# CPU-board-Sheet3-multi.net
KiCad netlist of a schematic drawn in Altium Designer
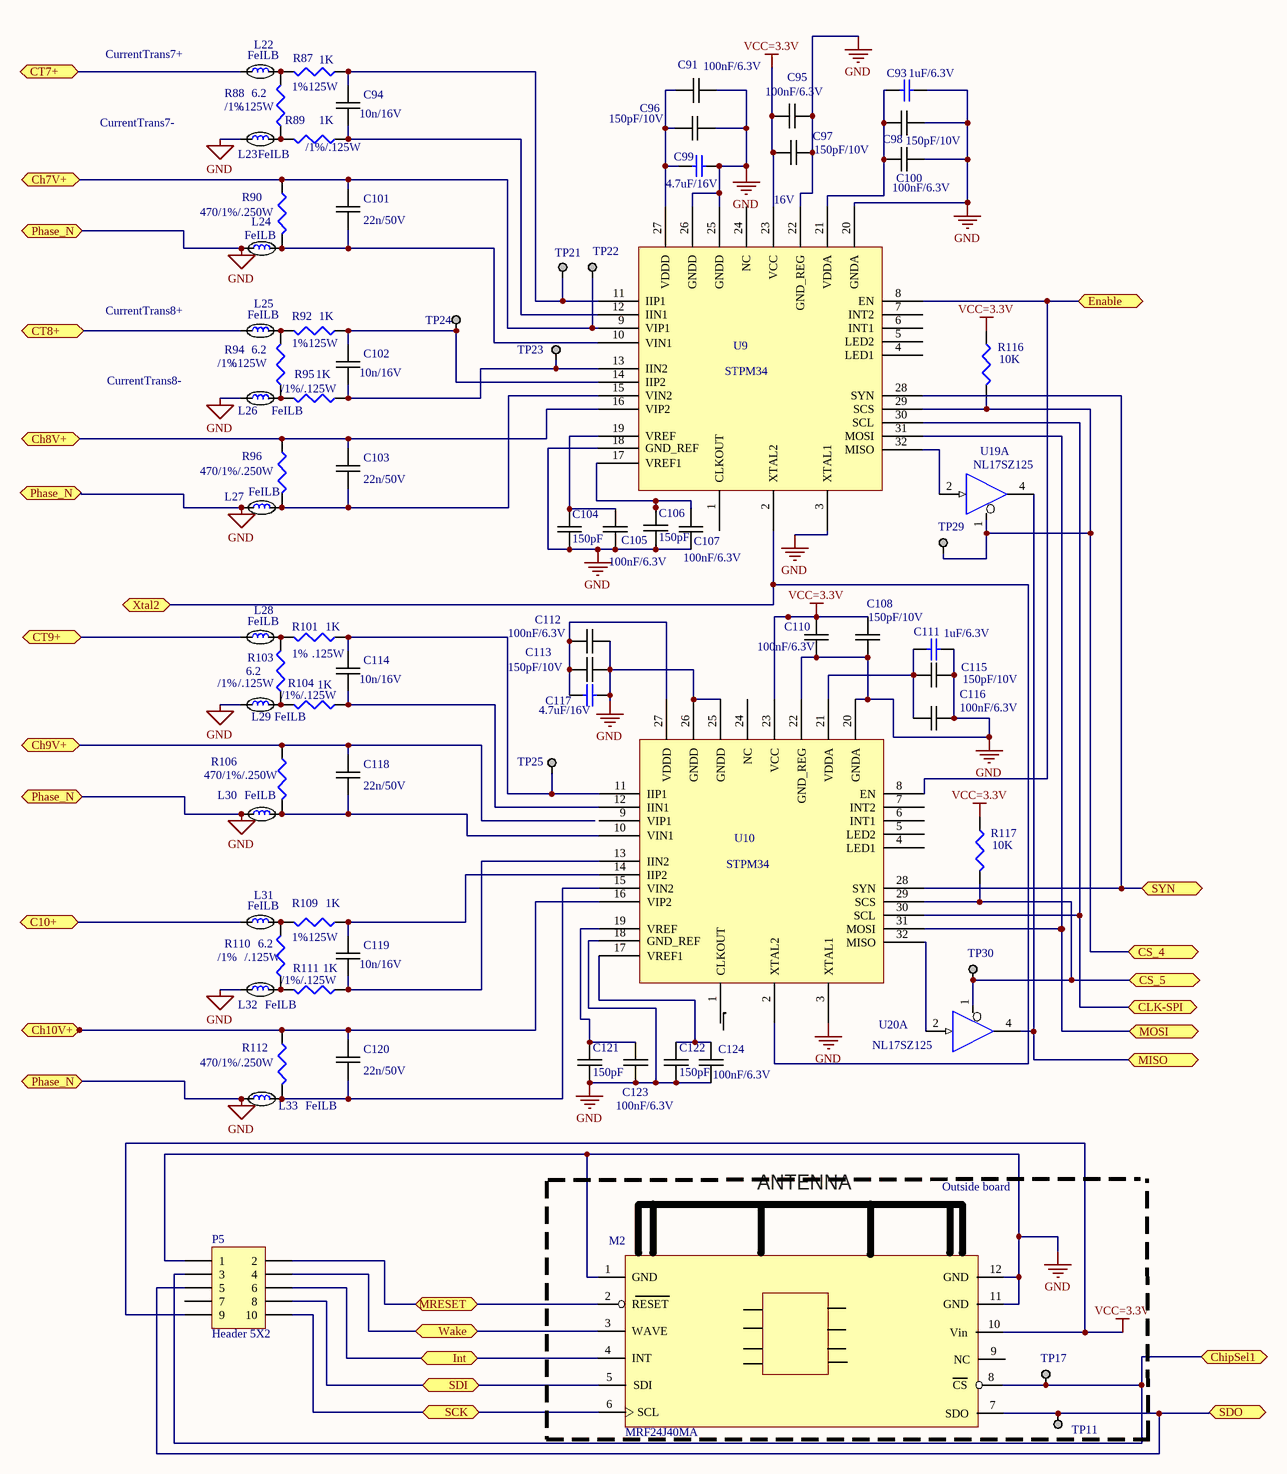
[diagram p0: CPU-board-Sheet3-multi.SchDoc]

(export (version "E")
  (design (tool "Eeschema 10.0.6"))
  (components
    (comp (ref "C91")
      (value "100nF/6.3V")
      (footprint "0402C-GENERIC")
      (description "CAPACITOR 0805 CERAMIC")
      (fields (field (name "MANUFACTURER") "Taiyo Yuden"))
      (libsource (lib "vh_altium_library") (part "0805C-18PF-50V-C0G-JOH"))
    )
    (comp (ref "C93")
      (value "1uF/6.3V")
      (footprint "0402C-GENERIC")
      (description "Capacitor")
      (fields (field (name "MANUFACTURER") "Murata") (field (name "PUBLISHER") "Altium Limited"))
      (libsource (lib "Miscellaneous Devices") (part "Cap"))
    )
    (comp (ref "C94")
      (value "10n/16V")
      (footprint "0402C-GENERIC")
      (description "CAPACITOR 0805 CERAMIC")
      (fields (field (name "MANUFACTURER") "Murata Electronics"))
      (libsource (lib "vh_altium_library") (part "0805C-18PF-50V-C0G-JOH"))
    )
    (comp (ref "C95")
      (value "100nF/6.3V")
      (footprint "0402C-GENERIC")
      (description "CAPACITOR 0805 CERAMIC")
      (fields (field (name "MANUFACTURER") "Taiyo Yuden"))
      (libsource (lib "vh_altium_library") (part "0805C-18PF-50V-C0G-JOH"))
    )
    (comp (ref "C96")
      (value "150pF/10V")
      (footprint "0402C-GENERIC")
      (description "CAPACITOR 0805 CERAMIC")
      (fields (field (name "MANUFACTURER") "Wurth Electronics"))
      (libsource (lib "vh_altium_library") (part "0805C-18PF-50V-C0G-JOH"))
    )
    (comp (ref "C97")
      (value "150pF/10V")
      (footprint "0402C-GENERIC")
      (description "CAPACITOR 0805 CERAMIC")
      (fields (field (name "MANUFACTURER") "Wurth Electronics"))
      (libsource (lib "vh_altium_library") (part "0805C-18PF-50V-C0G-JOH"))
    )
    (comp (ref "C98")
      (value "150pF/10V")
      (footprint "0402C-GENERIC")
      (description "CAPACITOR 0805 CERAMIC")
      (fields (field (name "MANUFACTURER") "Wurth Electronics"))
      (libsource (lib "vh_altium_library") (part "0805C-18PF-50V-C0G-JOH"))
    )
    (comp (ref "C99")
      (value "4.7uF/16V")
      (footprint "0402C-GENERIC")
      (description "Capacitor")
      (fields (field (name "MANUFACTURER") "Samsung") (field (name "PUBLISHER") "Altium Limited"))
      (libsource (lib "Miscellaneous Devices") (part "Cap"))
    )
    (comp (ref "C100")
      (value "100nF/6.3V")
      (footprint "0402C-GENERIC")
      (description "CAPACITOR 0805 CERAMIC")
      (fields (field (name "MANUFACTURER") "Taiyo Yuden"))
      (libsource (lib "vh_altium_library") (part "0805C-18PF-50V-C0G-JOH"))
    )
    (comp (ref "C101")
      (value "22n/50V")
      (footprint "0402C-GENERIC")
      (description "CAPACITOR 0805 CERAMIC")
      (fields (field (name "MANUFACTURER") "Murata Electronics"))
      (libsource (lib "vh_altium_library") (part "0805C-18PF-50V-C0G-JOH"))
    )
    (comp (ref "C102")
      (value "10n/16V")
      (footprint "0402C-GENERIC")
      (description "CAPACITOR 0805 CERAMIC")
      (fields (field (name "MANUFACTURER") "Murata Electronics"))
      (libsource (lib "vh_altium_library") (part "0805C-18PF-50V-C0G-JOH"))
    )
    (comp (ref "C103")
      (value "22n/50V")
      (footprint "0402C-GENERIC")
      (description "CAPACITOR 0805 CERAMIC")
      (fields (field (name "MANUFACTURER") "Murata Electronics"))
      (libsource (lib "vh_altium_library") (part "0805C-18PF-50V-C0G-JOH"))
    )
    (comp (ref "C104")
      (value "150pF")
      (footprint "0402C-GENERIC")
      (description "CAPACITOR 0805 CERAMIC")
      (fields (field (name "MANUFACTURER") "Wurth Electronics"))
      (libsource (lib "vh_altium_library") (part "0805C-18PF-50V-C0G-JOH"))
    )
    (comp (ref "C105")
      (value "100nF/6.3V")
      (footprint "0402C-GENERIC")
      (description "CAPACITOR 0805 CERAMIC")
      (fields (field (name "MANUFACTURER") "Taiyo Yuden"))
      (libsource (lib "vh_altium_library") (part "0805C-18PF-50V-C0G-JOH"))
    )
    (comp (ref "C106")
      (value "150pF")
      (footprint "0402C-GENERIC")
      (description "CAPACITOR 0805 CERAMIC")
      (fields (field (name "MANUFACTURER") "Wurth Electronics"))
      (libsource (lib "vh_altium_library") (part "0805C-18PF-50V-C0G-JOH"))
    )
    (comp (ref "C107")
      (value "100nF/6.3V")
      (footprint "0402C-GENERIC")
      (description "CAPACITOR 0805 CERAMIC")
      (fields (field (name "MANUFACTURER") "Taiyo Yuden"))
      (libsource (lib "vh_altium_library") (part "0805C-18PF-50V-C0G-JOH"))
    )
    (comp (ref "C108")
      (value "150pF/10V")
      (footprint "0402C-GENERIC")
      (description "CAPACITOR 0805 CERAMIC")
      (fields (field (name "MANUFACTURER") "Wurth Electronics"))
      (libsource (lib "vh_altium_library") (part "0805C-18PF-50V-C0G-JOH"))
    )
    (comp (ref "C110")
      (value "100nF/6.3V")
      (footprint "0402C-GENERIC")
      (description "CAPACITOR 0805 CERAMIC")
      (fields (field (name "MANUFACTURER") "Taiyo Yuden"))
      (libsource (lib "vh_altium_library") (part "0805C-18PF-50V-C0G-JOH"))
    )
    (comp (ref "C111")
      (value "1uF/6.3V")
      (footprint "0402C-GENERIC")
      (description "Capacitor")
      (fields (field (name "MANUFACTURER") "Murata") (field (name "PUBLISHER") "Altium Limited"))
      (libsource (lib "Miscellaneous Devices") (part "Cap"))
    )
    (comp (ref "C112")
      (value "100nF/6.3V")
      (footprint "0402C-GENERIC")
      (description "CAPACITOR 0805 CERAMIC")
      (fields (field (name "MANUFACTURER") "Taiyo Yuden"))
      (libsource (lib "vh_altium_library") (part "0805C-18PF-50V-C0G-JOH"))
    )
    (comp (ref "C113")
      (value "150pF/10V")
      (footprint "0402C-GENERIC")
      (description "CAPACITOR 0805 CERAMIC")
      (fields (field (name "MANUFACTURER") "Wurth Electronics"))
      (libsource (lib "vh_altium_library") (part "0805C-18PF-50V-C0G-JOH"))
    )
    (comp (ref "C114")
      (value "10n/16V")
      (footprint "0402C-GENERIC")
      (description "CAPACITOR 0805 CERAMIC")
      (fields (field (name "MANUFACTURER") "Murata Electronics"))
      (libsource (lib "vh_altium_library") (part "0805C-18PF-50V-C0G-JOH"))
    )
    (comp (ref "C115")
      (value "150pF/10V")
      (footprint "0402C-GENERIC")
      (description "CAPACITOR 0805 CERAMIC")
      (fields (field (name "MANUFACTURER") "Wurth Electronics"))
      (libsource (lib "vh_altium_library") (part "0805C-18PF-50V-C0G-JOH"))
    )
    (comp (ref "C116")
      (value "100nF/6.3V")
      (footprint "0402C-GENERIC")
      (description "CAPACITOR 0805 CERAMIC")
      (fields (field (name "MANUFACTURER") "Taiyo Yuden"))
      (libsource (lib "vh_altium_library") (part "0805C-18PF-50V-C0G-JOH"))
    )
    (comp (ref "C117")
      (value "4.7uF/16V")
      (footprint "0402C-GENERIC")
      (description "Capacitor")
      (fields (field (name "MANUFACTURER") "Samsung") (field (name "PUBLISHER") "Altium Limited"))
      (libsource (lib "Miscellaneous Devices") (part "Cap"))
    )
    (comp (ref "C118")
      (value "22n/50V")
      (footprint "0402C-GENERIC")
      (description "CAPACITOR 0805 CERAMIC")
      (fields (field (name "MANUFACTURER") "Murata Electronics"))
      (libsource (lib "vh_altium_library") (part "0805C-18PF-50V-C0G-JOH"))
    )
    (comp (ref "C119")
      (value "10n/16V")
      (footprint "0402C-GENERIC")
      (description "CAPACITOR 0805 CERAMIC")
      (fields (field (name "MANUFACTURER") "Murata Electronics"))
      (libsource (lib "vh_altium_library") (part "0805C-18PF-50V-C0G-JOH"))
    )
    (comp (ref "C120")
      (value "22n/50V")
      (footprint "0402C-GENERIC")
      (description "CAPACITOR 0805 CERAMIC")
      (fields (field (name "MANUFACTURER") "Murata Electronics"))
      (libsource (lib "vh_altium_library") (part "0805C-18PF-50V-C0G-JOH"))
    )
    (comp (ref "C121")
      (value "150pF")
      (footprint "0402C-GENERIC")
      (description "CAPACITOR 0805 CERAMIC")
      (fields (field (name "MANUFACTURER") "Wurth Electronics"))
      (libsource (lib "vh_altium_library") (part "0805C-18PF-50V-C0G-JOH"))
    )
    (comp (ref "C122")
      (value "150pF")
      (footprint "0402C-GENERIC")
      (description "CAPACITOR 0805 CERAMIC")
      (fields (field (name "MANUFACTURER") "Wurth Electronics"))
      (libsource (lib "vh_altium_library") (part "0805C-18PF-50V-C0G-JOH"))
    )
    (comp (ref "C123")
      (value "100nF/6.3V")
      (footprint "0402C-GENERIC")
      (description "CAPACITOR 0805 CERAMIC")
      (fields (field (name "MANUFACTURER") "Taiyo Yuden"))
      (libsource (lib "vh_altium_library") (part "0805C-18PF-50V-C0G-JOH"))
    )
    (comp (ref "C124")
      (value "100nF/6.3V")
      (footprint "0402C-GENERIC")
      (description "CAPACITOR 0805 CERAMIC")
      (fields (field (name "MANUFACTURER") "Taiyo Yuden"))
      (libsource (lib "vh_altium_library") (part "0805C-18PF-50V-C0G-JOH"))
    )
    (comp (ref "L22")
      (value "FeILB")
      (footprint "0603C-TBD")
      (fields (field (name "MANUFACTURER") "Brand Samsung"))
      (libsource (lib "SMLib") (part "FerrBeads/ILBB"))
    )
    (comp (ref "L23")
      (value "FeILB")
      (footprint "0603C-TBD")
      (fields (field (name "MANUFACTURER") "Brand Samsung"))
      (libsource (lib "SMLib") (part "FerrBeads/ILBB"))
    )
    (comp (ref "L24")
      (value "FeILB")
      (footprint "0603C-TBD")
      (fields (field (name "MANUFACTURER") "Brand Samsung"))
      (libsource (lib "SMLib") (part "FerrBeads/ILBB"))
    )
    (comp (ref "L25")
      (value "FeILB")
      (footprint "0603C-TBD")
      (fields (field (name "MANUFACTURER") "Brand Samsung"))
      (libsource (lib "SMLib") (part "FerrBeads/ILBB"))
    )
    (comp (ref "L26")
      (value "FeILB")
      (footprint "0603C-TBD")
      (fields (field (name "MANUFACTURER") "Brand Samsung"))
      (libsource (lib "SMLib") (part "FerrBeads/ILBB"))
    )
    (comp (ref "L27")
      (value "FeILB")
      (footprint "0603C-TBD")
      (fields (field (name "MANUFACTURER") "Brand Samsung"))
      (libsource (lib "SMLib") (part "FerrBeads/ILBB"))
    )
    (comp (ref "L28")
      (value "FeILB")
      (footprint "0603C-TBD")
      (fields (field (name "MANUFACTURER") "Brand Samsung"))
      (libsource (lib "SMLib") (part "FerrBeads/ILBB"))
    )
    (comp (ref "L29")
      (value "FeILB")
      (footprint "0603C-TBD")
      (fields (field (name "MANUFACTURER") "Brand Samsung"))
      (libsource (lib "SMLib") (part "FerrBeads/ILBB"))
    )
    (comp (ref "L30")
      (value "FeILB")
      (footprint "0603C-TBD")
      (fields (field (name "MANUFACTURER") "Brand Samsung"))
      (libsource (lib "SMLib") (part "FerrBeads/ILBB"))
    )
    (comp (ref "L31")
      (value "FeILB")
      (footprint "0603C-TBD")
      (fields (field (name "MANUFACTURER") "Brand Samsung"))
      (libsource (lib "SMLib") (part "FerrBeads/ILBB"))
    )
    (comp (ref "L32")
      (value "FeILB")
      (footprint "0603C-TBD")
      (fields (field (name "MANUFACTURER") "Brand Samsung"))
      (libsource (lib "SMLib") (part "FerrBeads/ILBB"))
    )
    (comp (ref "L33")
      (value "FeILB")
      (footprint "0603C-TBD")
      (fields (field (name "MANUFACTURER") "Brand Samsung"))
      (libsource (lib "SMLib") (part "FerrBeads/ILBB"))
    )
    (comp (ref "M2")
      (value "MRF24J40MA")
      (footprint "MRF24J40MA-zigBEE module")
      (fields (field (name "MANUFACTURER") "Microchip"))
      (libsource (lib "SMLib") (part "MRF24J40MA"))
    )
    (comp (ref "P5")
      (value "Header 5X2")
      (footprint "Header2x5 1.27mm pitch")
      (description "Header, 5-Pin, Dual row")
      (fields (field (name "MANUFACTURER") "Samtec Inc") (field (name "PUBLISHER") "Altium Limited"))
      (libsource (lib "Miscellaneous Connectors") (part "Header 5X2"))
    )
    (comp (ref "R87")
      (value "1K")
      (footprint "0402R-TBD")
      (description "Resistor")
      (fields (field (name "MANUFACTURER") "Panasonic") (field (name "PUBLISHER") "Altium Limited"))
      (libsource (lib "Miscellaneous Devices") (part "Res3"))
    )
    (comp (ref "R88")
      (value "6.2")
      (footprint "0402R-TBD")
      (description "Resistor")
      (fields (field (name "MANUFACTURER") "Vishay Dale") (field (name "PUBLISHER") "Altium Limited"))
      (libsource (lib "Miscellaneous Devices") (part "Res3"))
    )
    (comp (ref "R89")
      (value "1K")
      (footprint "0402R-TBD")
      (description "Resistor")
      (fields (field (name "MANUFACTURER") "Panasonic") (field (name "PUBLISHER") "Altium Limited"))
      (libsource (lib "Miscellaneous Devices") (part "Res3"))
    )
    (comp (ref "R90")
      (value "470/1%/.250W")
      (footprint "1206FB-GENERIC")
      (description "Resistor")
      (fields (field (name "MANUFACTURER") "Vishay/Draloric") (field (name "PUBLISHER") "Altium Limited"))
      (libsource (lib "Miscellaneous Devices") (part "Res3"))
    )
    (comp (ref "R92")
      (value "1K")
      (footprint "0402R-TBD")
      (description "Resistor")
      (fields (field (name "MANUFACTURER") "Panasonic") (field (name "PUBLISHER") "Altium Limited"))
      (libsource (lib "Miscellaneous Devices") (part "Res3"))
    )
    (comp (ref "R94")
      (value "6.2")
      (footprint "0402R-TBD")
      (description "Resistor")
      (fields (field (name "MANUFACTURER") "Vishay Dale") (field (name "PUBLISHER") "Altium Limited"))
      (libsource (lib "Miscellaneous Devices") (part "Res3"))
    )
    (comp (ref "R95")
      (value "1K")
      (footprint "0402R-TBD")
      (description "Resistor")
      (fields (field (name "MANUFACTURER") "Panasonic") (field (name "PUBLISHER") "Altium Limited"))
      (libsource (lib "Miscellaneous Devices") (part "Res3"))
    )
    (comp (ref "R96")
      (value "470/1%/.250W")
      (footprint "1206FB-GENERIC")
      (description "Resistor")
      (fields (field (name "MANUFACTURER") "Vishay/Draloric") (field (name "PUBLISHER") "Altium Limited"))
      (libsource (lib "Miscellaneous Devices") (part "Res3"))
    )
    (comp (ref "R101")
      (value "1K")
      (footprint "0402R-TBD")
      (description "Resistor")
      (fields (field (name "MANUFACTURER") "Panasonic") (field (name "PUBLISHER") "Altium Limited"))
      (libsource (lib "Miscellaneous Devices") (part "Res3"))
    )
    (comp (ref "R103")
      (value "6.2")
      (footprint "0402R-TBD")
      (description "Resistor")
      (fields (field (name "MANUFACTURER") "Vishay Dale") (field (name "PUBLISHER") "Altium Limited"))
      (libsource (lib "Miscellaneous Devices") (part "Res3"))
    )
    (comp (ref "R104")
      (value "1K")
      (footprint "0402R-TBD")
      (description "Resistor")
      (fields (field (name "MANUFACTURER") "Panasonic") (field (name "PUBLISHER") "Altium Limited"))
      (libsource (lib "Miscellaneous Devices") (part "Res3"))
    )
    (comp (ref "R106")
      (value "470/1%/.250W")
      (footprint "1206FB-GENERIC")
      (description "Resistor")
      (fields (field (name "MANUFACTURER") "Vishay/Draloric") (field (name "PUBLISHER") "Altium Limited"))
      (libsource (lib "Miscellaneous Devices") (part "Res3"))
    )
    (comp (ref "R109")
      (value "1K")
      (footprint "0402R-TBD")
      (description "Resistor")
      (fields (field (name "MANUFACTURER") "Panasonic") (field (name "PUBLISHER") "Altium Limited"))
      (libsource (lib "Miscellaneous Devices") (part "Res3"))
    )
    (comp (ref "R110")
      (value "6.2")
      (footprint "0402R-TBD")
      (description "Resistor")
      (fields (field (name "MANUFACTURER") "Vishay Dale") (field (name "PUBLISHER") "Altium Limited"))
      (libsource (lib "Miscellaneous Devices") (part "Res3"))
    )
    (comp (ref "R111")
      (value "1K")
      (footprint "0402R-TBD")
      (description "Resistor")
      (fields (field (name "MANUFACTURER") "Panasonic") (field (name "PUBLISHER") "Altium Limited"))
      (libsource (lib "Miscellaneous Devices") (part "Res3"))
    )
    (comp (ref "R112")
      (value "470/1%/.250W")
      (footprint "1206FB-GENERIC")
      (description "Resistor")
      (fields (field (name "MANUFACTURER") "Vishay/Draloric") (field (name "PUBLISHER") "Altium Limited"))
      (libsource (lib "Miscellaneous Devices") (part "Res3"))
    )
    (comp (ref "R116")
      (value "10K")
      (footprint "0402C-GENERIC")
      (description "Resistor")
      (fields (field (name "MANUFACTURER") "Panasonic") (field (name "PUBLISHER") "Altium Limited"))
      (libsource (lib "Miscellaneous Devices") (part "Res3"))
    )
    (comp (ref "R117")
      (value "10K")
      (footprint "0402C-GENERIC")
      (description "Resistor")
      (fields (field (name "MANUFACTURER") "Panasonic") (field (name "PUBLISHER") "Altium Limited"))
      (libsource (lib "Miscellaneous Devices") (part "Res3"))
    )
    (comp (ref "TP11")
      (value "TESTPOINT")
      (footprint "TESTPOINT")
      (description "TESTPOINT SCOPE GRABBER")
      (fields
        (field (name "MANUFACTURER PART NUMBER") "5010")
        (field (name "MANUFACTURER") "Keystone Electronics")
      )
      (libsource (lib "vh_altium_library") (part "TESTPOINT"))
    )
    (comp (ref "TP17")
      (value "TESTPOINT")
      (footprint "TESTPOINT")
      (description "TESTPOINT SCOPE GRABBER")
      (fields
        (field (name "MANUFACTURER PART NUMBER") "5010")
        (field (name "MANUFACTURER") "Keystone Electronics")
      )
      (libsource (lib "vh_altium_library") (part "TESTPOINT"))
    )
    (comp (ref "TP21")
      (value "TESTPOINT")
      (footprint "TESTPOINT")
      (description "TESTPOINT SCOPE GRABBER")
      (fields
        (field (name "MANUFACTURER PART NUMBER") "5010")
        (field (name "MANUFACTURER") "Keystone Electronics")
      )
      (libsource (lib "vh_altium_library") (part "TESTPOINT"))
    )
    (comp (ref "TP22")
      (value "TESTPOINT")
      (footprint "TESTPOINT")
      (description "TESTPOINT SCOPE GRABBER")
      (fields
        (field (name "MANUFACTURER PART NUMBER") "5010")
        (field (name "MANUFACTURER") "Keystone Electronics")
      )
      (libsource (lib "vh_altium_library") (part "TESTPOINT"))
    )
    (comp (ref "TP23")
      (value "TESTPOINT")
      (footprint "TESTPOINT")
      (description "TESTPOINT SCOPE GRABBER")
      (fields
        (field (name "MANUFACTURER PART NUMBER") "5010")
        (field (name "MANUFACTURER") "Keystone Electronics")
      )
      (libsource (lib "vh_altium_library") (part "TESTPOINT"))
    )
    (comp (ref "TP24")
      (value "TESTPOINT")
      (footprint "TESTPOINT")
      (description "TESTPOINT SCOPE GRABBER")
      (fields
        (field (name "MANUFACTURER PART NUMBER") "5010")
        (field (name "MANUFACTURER") "Keystone Electronics")
      )
      (libsource (lib "vh_altium_library") (part "TESTPOINT"))
    )
    (comp (ref "TP25")
      (value "TESTPOINT")
      (footprint "TESTPOINT")
      (description "TESTPOINT SCOPE GRABBER")
      (fields
        (field (name "MANUFACTURER PART NUMBER") "5010")
        (field (name "MANUFACTURER") "Keystone Electronics")
      )
      (libsource (lib "vh_altium_library") (part "TESTPOINT"))
    )
    (comp (ref "TP29")
      (value "TESTPOINT")
      (footprint "TESTPOINT")
      (description "TESTPOINT SCOPE GRABBER")
      (fields
        (field (name "MANUFACTURER PART NUMBER") "5010")
        (field (name "MANUFACTURER") "Keystone Electronics")
      )
      (libsource (lib "vh_altium_library") (part "TESTPOINT"))
    )
    (comp (ref "TP30")
      (value "TESTPOINT")
      (footprint "TESTPOINT")
      (description "TESTPOINT SCOPE GRABBER")
      (fields (field (name "MANUFACTURER") "Harwing Inc"))
      (libsource (lib "vh_altium_library") (part "TESTPOINT"))
    )
    (comp (ref "U9")
      (value "STPM34")
      (footprint "Atmel Microcontroller 8-Bit megaAVR:QFN32_L")
      (libsource (lib "SMLib") (part "STPM34"))
    )
    (comp (ref "U10")
      (value "STPM34")
      (footprint "Atmel Microcontroller 8-Bit megaAVR:QFN32_L")
      (libsource (lib "SMLib") (part "STPM34"))
    )
    (comp (ref "U19")
      (value "NL17SZ125")
      (description "Tristate Single Buffer")
      (fields (field (name "MANUFACTURER") "ON Semi"))
      (libsource (lib "ON Semi Logic Buffer Line Driver") (part "NL17SZ125"))
    )
    (comp (ref "U20")
      (value "NL17SZ125")
      (description "Tristate Single Buffer")
      (fields (field (name "MANUFACTURER") "ON Semi"))
      (libsource (lib "ON Semi Logic Buffer Line Driver") (part "NL17SZ125"))
    )
  )
  (nets
    (net (code "1") (name "/C10+") (class "Default")
      (node (ref "L31") (pin "1") (pinfunction "1_1") (pintype "passive"))
    )
    (net (code "2") (name "/CLK-SPI") (class "Default")
      (node (ref "U10") (pin "30") (pinfunction "SCL_30") (pintype "passive"))
      (node (ref "U9") (pin "30") (pinfunction "SCL_30") (pintype "passive"))
    )
    (net (code "3") (name "/CS_4") (class "Default")
      (node (ref "R116") (pin "2") (pinfunction "2_2") (pintype "passive"))
      (node (ref "TP29") (pin "1") (pinfunction "1_1") (pintype "passive"))
      (node (ref "U19") (pin "1") (pinfunction "1_1") (pintype "passive"))
      (node (ref "U9") (pin "29") (pinfunction "SCS_29") (pintype "passive"))
    )
    (net (code "4") (name "/CS_5") (class "Default")
      (node (ref "R117") (pin "2") (pinfunction "2_2") (pintype "passive"))
      (node (ref "TP30") (pin "1") (pinfunction "1_1") (pintype "passive"))
      (node (ref "U10") (pin "29") (pinfunction "SCS_29") (pintype "passive"))
      (node (ref "U20") (pin "1") (pinfunction "1_1") (pintype "passive"))
    )
    (net (code "5") (name "/CT7+") (class "Default")
      (node (ref "L22") (pin "1") (pinfunction "1_1") (pintype "passive"))
    )
    (net (code "6") (name "/CT8+") (class "Default")
      (node (ref "L25") (pin "1") (pinfunction "1_1") (pintype "passive"))
    )
    (net (code "7") (name "/CT9+") (class "Default")
      (node (ref "L28") (pin "1") (pinfunction "1_1") (pintype "passive"))
    )
    (net (code "8") (name "/Ch7V+") (class "Default")
      (node (ref "C101") (pin "2") (pintype "passive"))
      (node (ref "R90") (pin "1") (pinfunction "1_1") (pintype "passive"))
      (node (ref "TP22") (pin "1") (pinfunction "1_1") (pintype "passive"))
      (node (ref "U9") (pin "9") (pinfunction "VIP1_9") (pintype "passive"))
    )
    (net (code "9") (name "/Ch8V+") (class "Default")
      (node (ref "C103") (pin "2") (pintype "passive"))
      (node (ref "R96") (pin "1") (pinfunction "1_1") (pintype "passive"))
      (node (ref "U9") (pin "16") (pinfunction "VIP2_16") (pintype "passive"))
    )
    (net (code "10") (name "/Ch9V+") (class "Default")
      (node (ref "C118") (pin "2") (pintype "passive"))
      (node (ref "R106") (pin "1") (pinfunction "1_1") (pintype "passive"))
    )
    (net (code "11") (name "/Ch10V+") (class "Default")
      (node (ref "C120") (pin "2") (pintype "passive"))
      (node (ref "R112") (pin "1") (pinfunction "1_1") (pintype "passive"))
      (node (ref "U10") (pin "16") (pinfunction "VIP2_16") (pintype "passive"))
    )
    (net (code "12") (name "/ChipSel1") (class "Default")
      (node (ref "M2") (pin "8") (pinfunction "CS_8") (pintype "passive"))
      (node (ref "P5") (pin "3") (pinfunction "3_3") (pintype "passive"))
      (node (ref "TP17") (pin "1") (pinfunction "1_1") (pintype "passive"))
    )
    (net (code "13") (name "/Enable") (class "Default")
      (node (ref "U10") (pin "8") (pinfunction "EN_8") (pintype "passive"))
      (node (ref "U9") (pin "8") (pinfunction "EN_8") (pintype "passive"))
    )
    (net (code "14") (name "/Int") (class "Default")
      (node (ref "M2") (pin "4") (pinfunction "INT_4") (pintype "passive"))
      (node (ref "P5") (pin "6") (pinfunction "6_6") (pintype "passive"))
    )
    (net (code "15") (name "/MISO") (class "Default")
      (node (ref "U19") (pin "4") (pinfunction "Y_4") (pintype "passive"))
      (node (ref "U20") (pin "4") (pinfunction "Y_4") (pintype "passive"))
    )
    (net (code "16") (name "/MOSI") (class "Default")
      (node (ref "U10") (pin "31") (pinfunction "MOSI_31") (pintype "passive"))
      (node (ref "U9") (pin "31") (pinfunction "MOSI_31") (pintype "passive"))
    )
    (net (code "17") (name "/MRESET") (class "Default")
      (node (ref "M2") (pin "2") (pinfunction "RESET_2") (pintype "passive"))
      (node (ref "P5") (pin "2") (pinfunction "2_2") (pintype "passive"))
    )
    (net (code "18") (name "/SCK") (class "Default")
      (node (ref "M2") (pin "6") (pinfunction "SCL_6") (pintype "passive"))
      (node (ref "P5") (pin "10") (pinfunction "10_10") (pintype "passive"))
    )
    (net (code "19") (name "/SDI") (class "Default")
      (node (ref "M2") (pin "5") (pinfunction "SDI_5") (pintype "passive"))
      (node (ref "P5") (pin "8") (pinfunction "8_8") (pintype "passive"))
    )
    (net (code "20") (name "/SDO") (class "Default")
      (node (ref "M2") (pin "7") (pinfunction "SDO_7") (pintype "passive"))
      (node (ref "P5") (pin "5") (pinfunction "5_5") (pintype "passive"))
      (node (ref "TP11") (pin "1") (pinfunction "1_1") (pintype "passive"))
    )
    (net (code "21") (name "/SYN") (class "Default")
      (node (ref "U10") (pin "28") (pinfunction "SYN_28") (pintype "passive"))
      (node (ref "U9") (pin "28") (pinfunction "SYN_28") (pintype "passive"))
    )
    (net (code "22") (name "/Wake") (class "Default")
      (node (ref "M2") (pin "3") (pinfunction "WAVE_3") (pintype "passive"))
      (node (ref "P5") (pin "4") (pinfunction "4_4") (pintype "passive"))
    )
    (net (code "23") (name "/Xtal2") (class "Default")
      (node (ref "U10") (pin "2") (pinfunction "XTAL2_2") (pintype "passive"))
      (node (ref "U9") (pin "2") (pinfunction "XTAL2_2") (pintype "passive"))
    )
    (net (code "24") (name "GND") (class "Default")
      (node (ref "C100") (pin "2") (pintype "passive"))
      (node (ref "C104") (pin "2") (pintype "passive"))
      (node (ref "C105") (pin "2") (pintype "passive"))
      (node (ref "C106") (pin "2") (pintype "passive"))
      (node (ref "C107") (pin "2") (pintype "passive"))
      (node (ref "C108") (pin "2") (pintype "passive"))
      (node (ref "C110") (pin "1") (pintype "passive"))
      (node (ref "C111") (pin "2") (pinfunction "2_2") (pintype "passive"))
      (node (ref "C112") (pin "2") (pintype "passive"))
      (node (ref "C113") (pin "2") (pintype "passive"))
      (node (ref "C115") (pin "2") (pintype "passive"))
      (node (ref "C116") (pin "2") (pintype "passive"))
      (node (ref "C117") (pin "2") (pinfunction "2_2") (pintype "passive"))
      (node (ref "C121") (pin "2") (pintype "passive"))
      (node (ref "C122") (pin "2") (pintype "passive"))
      (node (ref "C123") (pin "2") (pintype "passive"))
      (node (ref "C124") (pin "2") (pintype "passive"))
      (node (ref "C91") (pin "2") (pintype "passive"))
      (node (ref "C93") (pin "2") (pinfunction "2_2") (pintype "passive"))
      (node (ref "C95") (pin "2") (pintype "passive"))
      (node (ref "C96") (pin "2") (pintype "passive"))
      (node (ref "C97") (pin "2") (pintype "passive"))
      (node (ref "C98") (pin "1") (pintype "passive"))
      (node (ref "C99") (pin "2") (pinfunction "2_2") (pintype "passive"))
      (node (ref "L23") (pin "1") (pinfunction "1_1") (pintype "passive"))
      (node (ref "L24") (pin "1") (pinfunction "1_1") (pintype "passive"))
      (node (ref "L26") (pin "1") (pinfunction "1_1") (pintype "passive"))
      (node (ref "L27") (pin "1") (pinfunction "1_1") (pintype "passive"))
      (node (ref "L29") (pin "1") (pinfunction "1_1") (pintype "passive"))
      (node (ref "L30") (pin "1") (pinfunction "1_1") (pintype "passive"))
      (node (ref "L32") (pin "1") (pinfunction "1_1") (pintype "passive"))
      (node (ref "L33") (pin "1") (pinfunction "1_1") (pintype "passive"))
      (node (ref "M2") (pin "1") (pinfunction "GND_1") (pintype "passive"))
      (node (ref "M2") (pin "11") (pinfunction "GND_11") (pintype "passive"))
      (node (ref "M2") (pin "12") (pinfunction "GND_12") (pintype "passive"))
      (node (ref "P5") (pin "1") (pinfunction "1_1") (pintype "passive"))
      (node (ref "U10") (pin "18") (pinfunction "GND_REF_18") (pintype "passive"))
      (node (ref "U10") (pin "20") (pinfunction "GNDA_20") (pintype "passive"))
      (node (ref "U10") (pin "22") (pinfunction "GND_REG_22") (pintype "passive"))
      (node (ref "U10") (pin "25") (pinfunction "GNDD_25") (pintype "passive"))
      (node (ref "U10") (pin "26") (pinfunction "GNDD_26") (pintype "passive"))
      (node (ref "U10") (pin "3") (pinfunction "XTAL1_3") (pintype "passive"))
      (node (ref "U9") (pin "18") (pinfunction "GND_REF_18") (pintype "passive"))
      (node (ref "U9") (pin "20") (pinfunction "GNDA_20") (pintype "passive"))
      (node (ref "U9") (pin "22") (pinfunction "GND_REG_22") (pintype "passive"))
      (node (ref "U9") (pin "25") (pinfunction "GNDD_25") (pintype "passive"))
      (node (ref "U9") (pin "26") (pinfunction "GNDD_26") (pintype "passive"))
      (node (ref "U9") (pin "3") (pinfunction "XTAL1_3") (pintype "passive"))
    )
    (net (code "25") (name "Net-(L22-Pad2)") (class "Default")
      (node (ref "L22") (pin "2") (pinfunction "2_2") (pintype "passive"))
      (node (ref "R87") (pin "2") (pinfunction "2_2") (pintype "passive"))
      (node (ref "R88") (pin "2") (pinfunction "2_2") (pintype "passive"))
    )
    (net (code "26") (name "Net-(L23-Pad2)") (class "Default")
      (node (ref "L23") (pin "2") (pinfunction "2_2") (pintype "passive"))
      (node (ref "R88") (pin "1") (pinfunction "1_1") (pintype "passive"))
      (node (ref "R89") (pin "2") (pinfunction "2_2") (pintype "passive"))
    )
    (net (code "27") (name "Net-(L25-Pad2)") (class "Default")
      (node (ref "L25") (pin "2") (pinfunction "2_2") (pintype "passive"))
      (node (ref "R92") (pin "2") (pinfunction "2_2") (pintype "passive"))
      (node (ref "R94") (pin "2") (pinfunction "2_2") (pintype "passive"))
    )
    (net (code "28") (name "Net-(L26-Pad2)") (class "Default")
      (node (ref "L26") (pin "2") (pinfunction "2_2") (pintype "passive"))
      (node (ref "R94") (pin "1") (pinfunction "1_1") (pintype "passive"))
      (node (ref "R95") (pin "2") (pinfunction "2_2") (pintype "passive"))
    )
    (net (code "29") (name "Net-(L28-Pad2)") (class "Default")
      (node (ref "L28") (pin "2") (pinfunction "2_2") (pintype "passive"))
      (node (ref "R101") (pin "2") (pinfunction "2_2") (pintype "passive"))
      (node (ref "R103") (pin "2") (pinfunction "2_2") (pintype "passive"))
    )
    (net (code "30") (name "Net-(L29-Pad2)") (class "Default")
      (node (ref "L29") (pin "2") (pinfunction "2_2") (pintype "passive"))
      (node (ref "R103") (pin "1") (pinfunction "1_1") (pintype "passive"))
      (node (ref "R104") (pin "2") (pinfunction "2_2") (pintype "passive"))
    )
    (net (code "31") (name "Net-(L31-Pad2)") (class "Default")
      (node (ref "L31") (pin "2") (pinfunction "2_2") (pintype "passive"))
      (node (ref "R109") (pin "2") (pinfunction "2_2") (pintype "passive"))
      (node (ref "R110") (pin "2") (pinfunction "2_2") (pintype "passive"))
    )
    (net (code "32") (name "Net-(L32-Pad2)") (class "Default")
      (node (ref "L32") (pin "2") (pinfunction "2_2") (pintype "passive"))
      (node (ref "R110") (pin "1") (pinfunction "1_1") (pintype "passive"))
      (node (ref "R111") (pin "2") (pinfunction "2_2") (pintype "passive"))
    )
    (net (code "33") (name "Net-(U9-IIN1)") (class "Default")
      (node (ref "C94") (pin "1") (pintype "passive"))
      (node (ref "R89") (pin "1") (pinfunction "1_1") (pintype "passive"))
      (node (ref "U9") (pin "12") (pinfunction "IIN1_12") (pintype "passive"))
    )
    (net (code "34") (name "Net-(U9-IIN2)") (class "Default")
      (node (ref "C102") (pin "1") (pintype "passive"))
      (node (ref "R95") (pin "1") (pinfunction "1_1") (pintype "passive"))
      (node (ref "TP23") (pin "1") (pinfunction "1_1") (pintype "passive"))
      (node (ref "U9") (pin "13") (pinfunction "IIN2_13") (pintype "passive"))
    )
    (net (code "35") (name "Net-(U9-IIP1)") (class "Default")
      (node (ref "C94") (pin "2") (pintype "passive"))
      (node (ref "R87") (pin "1") (pinfunction "1_1") (pintype "passive"))
      (node (ref "TP21") (pin "1") (pinfunction "1_1") (pintype "passive"))
      (node (ref "U9") (pin "11") (pinfunction "IIP1_11") (pintype "passive"))
    )
    (net (code "36") (name "Net-(U9-IIP2)") (class "Default")
      (node (ref "C102") (pin "2") (pintype "passive"))
      (node (ref "R92") (pin "1") (pinfunction "1_1") (pintype "passive"))
      (node (ref "TP24") (pin "1") (pinfunction "1_1") (pintype "passive"))
      (node (ref "U9") (pin "14") (pinfunction "IIP2_14") (pintype "passive"))
    )
    (net (code "37") (name "Net-(U9-VDDA)") (class "Default")
      (node (ref "C100") (pin "1") (pintype "passive"))
      (node (ref "C93") (pin "1") (pinfunction "1_1") (pintype "passive"))
      (node (ref "C98") (pin "2") (pintype "passive"))
      (node (ref "U9") (pin "21") (pinfunction "VDDA_21") (pintype "passive"))
    )
    (net (code "38") (name "Net-(U9-VDDD)") (class "Default")
      (node (ref "C91") (pin "1") (pintype "passive"))
      (node (ref "C96") (pin "1") (pintype "passive"))
      (node (ref "C99") (pin "1") (pinfunction "1_1") (pintype "passive"))
      (node (ref "U9") (pin "27") (pinfunction "VDDD_27") (pintype "passive"))
    )
    (net (code "39") (name "Net-(U9-VIN1)") (class "Default")
      (node (ref "C101") (pin "1") (pintype "passive"))
      (node (ref "L24") (pin "2") (pinfunction "2_2") (pintype "passive"))
      (node (ref "R90") (pin "2") (pinfunction "2_2") (pintype "passive"))
      (node (ref "U9") (pin "10") (pinfunction "VIN1_10") (pintype "passive"))
    )
    (net (code "40") (name "Net-(U9-VIN2)") (class "Default")
      (node (ref "C103") (pin "1") (pintype "passive"))
      (node (ref "L27") (pin "2") (pinfunction "2_2") (pintype "passive"))
      (node (ref "R96") (pin "2") (pinfunction "2_2") (pintype "passive"))
      (node (ref "U9") (pin "15") (pinfunction "VIN2_15") (pintype "passive"))
    )
    (net (code "41") (name "Net-(U9-VREF)") (class "Default")
      (node (ref "C104") (pin "1") (pintype "passive"))
      (node (ref "C105") (pin "1") (pintype "passive"))
      (node (ref "U9") (pin "19") (pinfunction "VREF_19") (pintype "passive"))
    )
    (net (code "42") (name "Net-(U9-VREF1)") (class "Default")
      (node (ref "C106") (pin "1") (pintype "passive"))
      (node (ref "C107") (pin "1") (pintype "passive"))
      (node (ref "U9") (pin "17") (pinfunction "VREF1_17") (pintype "passive"))
    )
    (net (code "43") (name "Net-(U10-IIN1)") (class "Default")
      (node (ref "C114") (pin "1") (pintype "passive"))
      (node (ref "R104") (pin "1") (pinfunction "1_1") (pintype "passive"))
      (node (ref "U10") (pin "12") (pinfunction "IIN1_12") (pintype "passive"))
    )
    (net (code "44") (name "Net-(U10-IIN2)") (class "Default")
      (node (ref "C119") (pin "1") (pintype "passive"))
      (node (ref "R111") (pin "1") (pinfunction "1_1") (pintype "passive"))
      (node (ref "U10") (pin "13") (pinfunction "IIN2_13") (pintype "passive"))
    )
    (net (code "45") (name "Net-(U10-IIP1)") (class "Default")
      (node (ref "C114") (pin "2") (pintype "passive"))
      (node (ref "R101") (pin "1") (pinfunction "1_1") (pintype "passive"))
      (node (ref "TP25") (pin "1") (pinfunction "1_1") (pintype "passive"))
      (node (ref "U10") (pin "11") (pinfunction "IIP1_11") (pintype "passive"))
    )
    (net (code "46") (name "Net-(U10-IIP2)") (class "Default")
      (node (ref "C119") (pin "2") (pintype "passive"))
      (node (ref "R109") (pin "1") (pinfunction "1_1") (pintype "passive"))
      (node (ref "U10") (pin "14") (pinfunction "IIP2_14") (pintype "passive"))
    )
    (net (code "47") (name "Net-(U10-MISO)") (class "Default")
      (node (ref "U10") (pin "32") (pinfunction "MISO_32") (pintype "passive"))
      (node (ref "U20") (pin "2") (pinfunction "B_2") (pintype "input"))
    )
    (net (code "48") (name "Net-(U10-VDDA)") (class "Default")
      (node (ref "C111") (pin "1") (pinfunction "1_1") (pintype "passive"))
      (node (ref "C115") (pin "1") (pintype "passive"))
      (node (ref "C116") (pin "1") (pintype "passive"))
      (node (ref "U10") (pin "21") (pinfunction "VDDA_21") (pintype "passive"))
    )
    (net (code "49") (name "Net-(U10-VDDD)") (class "Default")
      (node (ref "C112") (pin "1") (pintype "passive"))
      (node (ref "C113") (pin "1") (pintype "passive"))
      (node (ref "C117") (pin "1") (pinfunction "1_1") (pintype "passive"))
      (node (ref "U10") (pin "27") (pinfunction "VDDD_27") (pintype "passive"))
    )
    (net (code "50") (name "Net-(U10-VIN1)") (class "Default")
      (node (ref "C118") (pin "1") (pintype "passive"))
      (node (ref "L30") (pin "2") (pinfunction "2_2") (pintype "passive"))
      (node (ref "R106") (pin "2") (pinfunction "2_2") (pintype "passive"))
      (node (ref "U10") (pin "10") (pinfunction "VIN1_10") (pintype "passive"))
    )
    (net (code "51") (name "Net-(U10-VIN2)") (class "Default")
      (node (ref "C120") (pin "1") (pintype "passive"))
      (node (ref "L33") (pin "2") (pinfunction "2_2") (pintype "passive"))
      (node (ref "R112") (pin "2") (pinfunction "2_2") (pintype "passive"))
      (node (ref "U10") (pin "15") (pinfunction "VIN2_15") (pintype "passive"))
    )
    (net (code "52") (name "Net-(U10-VREF)") (class "Default")
      (node (ref "C121") (pin "1") (pintype "passive"))
      (node (ref "C123") (pin "1") (pintype "passive"))
      (node (ref "U10") (pin "19") (pinfunction "VREF_19") (pintype "passive"))
    )
    (net (code "53") (name "Net-(U10-VREF1)") (class "Default")
      (node (ref "C122") (pin "1") (pintype "passive"))
      (node (ref "C124") (pin "1") (pintype "passive"))
      (node (ref "U10") (pin "17") (pinfunction "VREF1_17") (pintype "passive"))
    )
    (net (code "54") (name "Net-(U19A-B)") (class "Default")
      (node (ref "U19") (pin "2") (pinfunction "B_2") (pintype "input"))
      (node (ref "U9") (pin "32") (pinfunction "MISO_32") (pintype "passive"))
    )
    (net (code "55") (name "VCC=3.3V") (class "Default")
      (node (ref "C108") (pin "1") (pintype "passive"))
      (node (ref "C110") (pin "2") (pintype "passive"))
      (node (ref "C95") (pin "1") (pintype "passive"))
      (node (ref "C97") (pin "1") (pintype "passive"))
      (node (ref "M2") (pin "10") (pinfunction "Vin_10") (pintype "passive"))
      (node (ref "P5") (pin "9") (pinfunction "9_9") (pintype "passive"))
      (node (ref "R116") (pin "1") (pinfunction "1_1") (pintype "passive"))
      (node (ref "R117") (pin "1") (pinfunction "1_1") (pintype "passive"))
      (node (ref "U10") (pin "23") (pinfunction "VCC_23") (pintype "passive"))
      (node (ref "U9") (pin "23") (pinfunction "VCC_23") (pintype "passive"))
    )
    (net (code "56") (name "unconnected-(M2-NC-Pad9)") (class "Default")
      (node (ref "M2") (pin "9") (pinfunction "NC_9") (pintype "passive"))
    )
    (net (code "57") (name "unconnected-(P5-Pad7)") (class "Default")
      (node (ref "P5") (pin "7") (pinfunction "7_7") (pintype "passive"))
    )
    (net (code "58") (name "unconnected-(U9-CLKOUT-Pad1)") (class "Default")
      (node (ref "U9") (pin "1") (pinfunction "CLKOUT_1") (pintype "passive"))
    )
    (net (code "59") (name "unconnected-(U9-INT1-Pad6)") (class "Default")
      (node (ref "U9") (pin "6") (pinfunction "INT1_6") (pintype "passive"))
    )
    (net (code "60") (name "unconnected-(U9-INT2-Pad7)") (class "Default")
      (node (ref "U9") (pin "7") (pinfunction "INT2_7") (pintype "passive"))
    )
    (net (code "61") (name "unconnected-(U9-LED1-Pad4)") (class "Default")
      (node (ref "U9") (pin "4") (pinfunction "LED1_4") (pintype "passive"))
    )
    (net (code "62") (name "unconnected-(U9-LED2-Pad5)") (class "Default")
      (node (ref "U9") (pin "5") (pinfunction "LED2_5") (pintype "passive"))
    )
    (net (code "63") (name "unconnected-(U9-NC-Pad24)") (class "Default")
      (node (ref "U9") (pin "24") (pinfunction "NC_24") (pintype "passive"))
    )
    (net (code "64") (name "unconnected-(U10-CLKOUT-Pad1)") (class "Default")
      (node (ref "U10") (pin "1") (pinfunction "CLKOUT_1") (pintype "passive"))
    )
    (net (code "65") (name "unconnected-(U10-INT1-Pad6)") (class "Default")
      (node (ref "U10") (pin "6") (pinfunction "INT1_6") (pintype "passive"))
    )
    (net (code "66") (name "unconnected-(U10-INT2-Pad7)") (class "Default")
      (node (ref "U10") (pin "7") (pinfunction "INT2_7") (pintype "passive"))
    )
    (net (code "67") (name "unconnected-(U10-LED1-Pad4)") (class "Default")
      (node (ref "U10") (pin "4") (pinfunction "LED1_4") (pintype "passive"))
    )
    (net (code "68") (name "unconnected-(U10-LED2-Pad5)") (class "Default")
      (node (ref "U10") (pin "5") (pinfunction "LED2_5") (pintype "passive"))
    )
    (net (code "69") (name "unconnected-(U10-NC-Pad24)") (class "Default")
      (node (ref "U10") (pin "24") (pinfunction "NC_24") (pintype "passive"))
    )
    (net (code "70") (name "unconnected-(U10-VIP1-Pad9)") (class "Default")
      (node (ref "U10") (pin "9") (pinfunction "VIP1_9") (pintype "passive"))
    )
  )
)
